# RGB_i2c_v4plusRTC.net
KiCad netlist of a schematic drawn in EAGLE
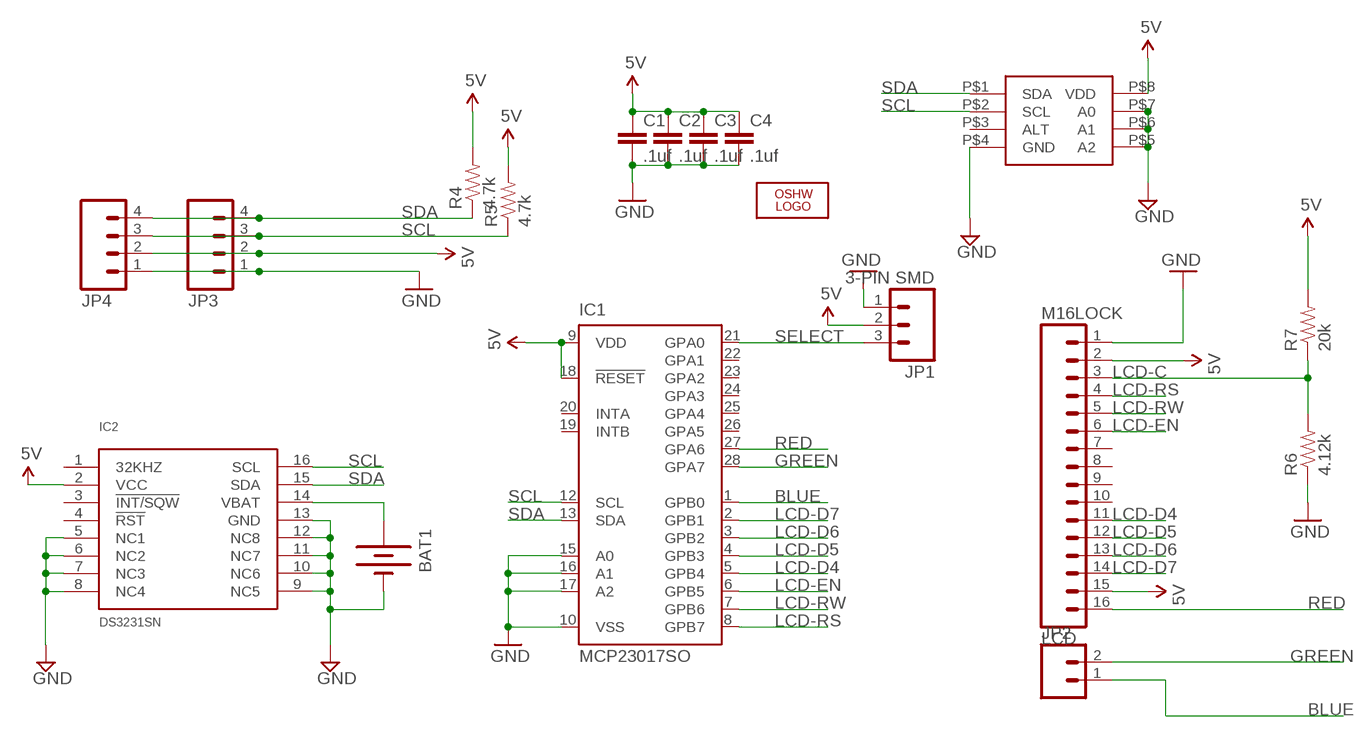
[diagram p0: schematic, sheet 1]

(export (version "E")
  (design (tool "Eeschema 10.0.6"))
  (components
    (comp (ref "BAT1")
      (value "BATTERY12MM")
      (footprint "eagle-import:BATTCON_12MM")
      (libsource (lib "eagle-import") (part "BATTERY12MM"))
    )
    (comp (ref "C1")
      (value ".1uf")
      (footprint "eagle-import:0805")
      (libsource (lib "eagle-import") (part "CAP0805"))
    )
    (comp (ref "C2")
      (value ".1uf")
      (footprint "eagle-import:0805")
      (libsource (lib "eagle-import") (part "CAP0805"))
    )
    (comp (ref "C3")
      (value ".1uf")
      (footprint "eagle-import:0805")
      (libsource (lib "eagle-import") (part "CAP0805"))
    )
    (comp (ref "C4")
      (value ".1uf")
      (footprint "eagle-import:0805")
      (libsource (lib "eagle-import") (part "CAP0805"))
    )
    (comp (ref "IC1")
      (value "MCP23017SO")
      (footprint "eagle-import:SO28W")
      (libsource (lib "eagle-import") (part "MCP23017SO"))
    )
    (comp (ref "IC2")
      (value "DS3231SN")
      (footprint "eagle-import:SO16W")
      (libsource (lib "eagle-import") (part "DS3231SN"))
    )
    (comp (ref "IC3")
      (value "MCP9808")
      (footprint "eagle-import:MSOP8")
      (libsource (lib "eagle-import") (part "MCP9808"))
    )
    (comp (ref "JP1")
      (value "3-PIN SMD")
      (footprint "eagle-import:JST-3-SMD")
      (libsource (lib "eagle-import") (part "M03JST-SMD"))
    )
    (comp (ref "JP2")
      (value "M02PTH")
      (footprint "eagle-import:1X02")
      (libsource (lib "eagle-import") (part "M02PTH"))
    )
    (comp (ref "JP3")
      (value "M04JST-PTH-VERT")
      (footprint "eagle-import:JST-4-PTH-VERT")
      (libsource (lib "eagle-import") (part "M04JST-PTH-VERT"))
    )
    (comp (ref "JP4")
      (value "M04JST-PTH-VERT")
      (footprint "eagle-import:JST-4-PTH-VERT")
      (libsource (lib "eagle-import") (part "M04JST-PTH-VERT"))
    )
    (comp (ref "LCD")
      (value "M16LOCK")
      (footprint "eagle-import:1X16_LOCK")
      (libsource (lib "eagle-import") (part "M16LOCK"))
    )
    (comp (ref "LOGO2")
      (value "OSHW_LOGO_10MILX0350-NT")
      (footprint "eagle-import:OSHW_10X350_NOTEXT")
      (libsource (lib "eagle-import") (part "OSHW_LOGO_10MILX0350-NT"))
    )
    (comp (ref "R4")
      (value "4.7k")
      (footprint "eagle-import:0805")
      (libsource (lib "eagle-import") (part "RESISTOR0805-RES"))
    )
    (comp (ref "R5")
      (value "4.7k")
      (footprint "eagle-import:0805")
      (libsource (lib "eagle-import") (part "RESISTOR0805-RES"))
    )
    (comp (ref "R6")
      (value "4.12k")
      (footprint "eagle-import:0805")
      (libsource (lib "eagle-import") (part "RESISTOR0805-RES"))
    )
    (comp (ref "R7")
      (value "20k")
      (footprint "eagle-import:0805")
      (libsource (lib "eagle-import") (part "RESISTOR0805-RES"))
    )
  )
  (nets
    (net (code "1") (name "/BLUE") (class "Default")
      (node (ref "IC1") (pin "1") (pinfunction "GPB0_1") (pintype "bidirectional"))
      (node (ref "JP2") (pin "1") (pinfunction "1_1") (pintype "passive"))
    )
    (net (code "2") (name "/GREEN") (class "Default")
      (node (ref "IC1") (pin "28") (pinfunction "GPA7_28") (pintype "bidirectional"))
      (node (ref "JP2") (pin "2") (pinfunction "2_2") (pintype "passive"))
    )
    (net (code "3") (name "/LCD-C") (class "Default")
      (node (ref "LCD") (pin "3") (pinfunction "3_3") (pintype "passive"))
      (node (ref "R6") (pin "2") (pinfunction "2_2") (pintype "passive"))
      (node (ref "R7") (pin "1") (pinfunction "1_1") (pintype "passive"))
    )
    (net (code "4") (name "/LCD-D4") (class "Default")
      (node (ref "IC1") (pin "5") (pinfunction "GPB4_5") (pintype "bidirectional"))
      (node (ref "LCD") (pin "11") (pinfunction "11_11") (pintype "passive"))
    )
    (net (code "5") (name "/LCD-D5") (class "Default")
      (node (ref "IC1") (pin "4") (pinfunction "GPB3_4") (pintype "bidirectional"))
      (node (ref "LCD") (pin "12") (pinfunction "12_12") (pintype "passive"))
    )
    (net (code "6") (name "/LCD-D6") (class "Default")
      (node (ref "IC1") (pin "3") (pinfunction "GPB2_3") (pintype "bidirectional"))
      (node (ref "LCD") (pin "13") (pinfunction "13_13") (pintype "passive"))
    )
    (net (code "7") (name "/LCD-D7") (class "Default")
      (node (ref "IC1") (pin "2") (pinfunction "GPB1_2") (pintype "bidirectional"))
      (node (ref "LCD") (pin "14") (pinfunction "14_14") (pintype "passive"))
    )
    (net (code "8") (name "/LCD-EN") (class "Default")
      (node (ref "IC1") (pin "6") (pinfunction "GPB5_6") (pintype "bidirectional"))
      (node (ref "LCD") (pin "6") (pinfunction "6_6") (pintype "passive"))
    )
    (net (code "9") (name "/LCD-RS") (class "Default")
      (node (ref "IC1") (pin "8") (pinfunction "GPB7_8") (pintype "bidirectional"))
      (node (ref "LCD") (pin "4") (pinfunction "4_4") (pintype "passive"))
    )
    (net (code "10") (name "/LCD-RW") (class "Default")
      (node (ref "IC1") (pin "7") (pinfunction "GPB6_7") (pintype "bidirectional"))
      (node (ref "LCD") (pin "5") (pinfunction "5_5") (pintype "passive"))
    )
    (net (code "11") (name "/RED") (class "Default")
      (node (ref "IC1") (pin "27") (pinfunction "GPA6_27") (pintype "bidirectional"))
      (node (ref "LCD") (pin "16") (pinfunction "16_16") (pintype "passive"))
    )
    (net (code "12") (name "/SCL") (class "Default")
      (node (ref "IC1") (pin "12") (pinfunction "SCL_12") (pintype "input"))
      (node (ref "IC2") (pin "16") (pinfunction "SCL_16") (pintype "bidirectional"))
      (node (ref "IC3") (pin "P$2") (pinfunction "SCL_P$2") (pintype "bidirectional"))
      (node (ref "JP3") (pin "3") (pinfunction "2_3") (pintype "passive"))
      (node (ref "JP4") (pin "3") (pinfunction "2_3") (pintype "passive"))
      (node (ref "R5") (pin "1") (pinfunction "1_1") (pintype "passive"))
    )
    (net (code "13") (name "/SDA") (class "Default")
      (node (ref "IC1") (pin "13") (pinfunction "SDA_13") (pintype "bidirectional"))
      (node (ref "IC2") (pin "15") (pinfunction "SDA_15") (pintype "bidirectional"))
      (node (ref "IC3") (pin "P$1") (pinfunction "SDA_P$1") (pintype "bidirectional"))
      (node (ref "JP3") (pin "4") (pinfunction "1_4") (pintype "passive"))
      (node (ref "JP4") (pin "4") (pinfunction "1_4") (pintype "passive"))
      (node (ref "R4") (pin "1") (pinfunction "1_1") (pintype "passive"))
    )
    (net (code "14") (name "/SELECT") (class "Default")
      (node (ref "IC1") (pin "21") (pinfunction "GPA0_21") (pintype "bidirectional"))
      (node (ref "JP1") (pin "3") (pinfunction "3_3") (pintype "passive"))
    )
    (net (code "15") (name "5V") (class "Default")
      (node (ref "C1") (pin "1") (pinfunction "1_1") (pintype "passive"))
      (node (ref "C2") (pin "1") (pinfunction "1_1") (pintype "passive"))
      (node (ref "C3") (pin "1") (pinfunction "1_1") (pintype "passive"))
      (node (ref "C4") (pin "1") (pinfunction "1_1") (pintype "passive"))
      (node (ref "IC1") (pin "18") (pinfunction "~{RESET}_18") (pintype "input"))
      (node (ref "IC1") (pin "9") (pinfunction "VDD_9") (pintype "power_in"))
      (node (ref "IC2") (pin "2") (pinfunction "VCC_2") (pintype "bidirectional"))
      (node (ref "IC3") (pin "P$8") (pinfunction "VDD_P$8") (pintype "bidirectional"))
      (node (ref "JP1") (pin "2") (pinfunction "2_2") (pintype "passive"))
      (node (ref "JP3") (pin "2") (pinfunction "3_2") (pintype "passive"))
      (node (ref "JP4") (pin "2") (pinfunction "3_2") (pintype "passive"))
      (node (ref "LCD") (pin "15") (pinfunction "15_15") (pintype "passive"))
      (node (ref "LCD") (pin "2") (pinfunction "2_2") (pintype "passive"))
      (node (ref "R4") (pin "2") (pinfunction "2_2") (pintype "passive"))
      (node (ref "R5") (pin "2") (pinfunction "2_2") (pintype "passive"))
      (node (ref "R7") (pin "2") (pinfunction "2_2") (pintype "passive"))
    )
    (net (code "16") (name "GND") (class "Default")
      (node (ref "BAT1") (pin "GND") (pinfunction "-_GND") (pintype "power_in"))
      (node (ref "C1") (pin "2") (pinfunction "2_2") (pintype "passive"))
      (node (ref "C2") (pin "2") (pinfunction "2_2") (pintype "passive"))
      (node (ref "C3") (pin "2") (pinfunction "2_2") (pintype "passive"))
      (node (ref "C4") (pin "2") (pinfunction "2_2") (pintype "passive"))
      (node (ref "IC1") (pin "10") (pinfunction "VSS_10") (pintype "power_in"))
      (node (ref "IC1") (pin "15") (pinfunction "A0_15") (pintype "input"))
      (node (ref "IC1") (pin "16") (pinfunction "A1_16") (pintype "input"))
      (node (ref "IC1") (pin "17") (pinfunction "A2_17") (pintype "input"))
      (node (ref "IC2") (pin "10") (pinfunction "NC6_10") (pintype "bidirectional"))
      (node (ref "IC2") (pin "11") (pinfunction "NC7_11") (pintype "bidirectional"))
      (node (ref "IC2") (pin "12") (pinfunction "NC8_12") (pintype "bidirectional"))
      (node (ref "IC2") (pin "13") (pinfunction "GND_13") (pintype "bidirectional"))
      (node (ref "IC2") (pin "5") (pinfunction "NC1_5") (pintype "bidirectional"))
      (node (ref "IC2") (pin "6") (pinfunction "NC2_6") (pintype "bidirectional"))
      (node (ref "IC2") (pin "7") (pinfunction "NC3_7") (pintype "bidirectional"))
      (node (ref "IC2") (pin "8") (pinfunction "NC4_8") (pintype "bidirectional"))
      (node (ref "IC2") (pin "9") (pinfunction "NC5_9") (pintype "bidirectional"))
      (node (ref "IC3") (pin "P$4") (pinfunction "GND_P$4") (pintype "bidirectional"))
      (node (ref "IC3") (pin "P$5") (pinfunction "A2_P$5") (pintype "bidirectional"))
      (node (ref "IC3") (pin "P$6") (pinfunction "A1_P$6") (pintype "bidirectional"))
      (node (ref "IC3") (pin "P$7") (pinfunction "A0_P$7") (pintype "bidirectional"))
      (node (ref "JP1") (pin "1") (pinfunction "1_1") (pintype "passive"))
      (node (ref "JP3") (pin "1") (pinfunction "4_1") (pintype "passive"))
      (node (ref "JP4") (pin "1") (pinfunction "4_1") (pintype "passive"))
      (node (ref "LCD") (pin "1") (pinfunction "1_1") (pintype "passive"))
      (node (ref "R6") (pin "1") (pinfunction "1_1") (pintype "passive"))
    )
    (net (code "17") (name "Net-(BAT1-+)") (class "Default")
      (node (ref "BAT1") (pin "PWR@1") (pinfunction "+_PWR@1") (pintype "power_in"))
      (node (ref "IC2") (pin "14") (pinfunction "VBAT_14") (pintype "bidirectional"))
    )
    (net (code "18") (name "unconnected-(IC1-GPA1-Pad22)") (class "Default")
      (node (ref "IC1") (pin "22") (pinfunction "GPA1_22") (pintype "bidirectional"))
    )
    (net (code "19") (name "unconnected-(IC1-GPA2-Pad23)") (class "Default")
      (node (ref "IC1") (pin "23") (pinfunction "GPA2_23") (pintype "bidirectional"))
    )
    (net (code "20") (name "unconnected-(IC1-GPA3-Pad24)") (class "Default")
      (node (ref "IC1") (pin "24") (pinfunction "GPA3_24") (pintype "bidirectional"))
    )
    (net (code "21") (name "unconnected-(IC1-GPA4-Pad25)") (class "Default")
      (node (ref "IC1") (pin "25") (pinfunction "GPA4_25") (pintype "bidirectional"))
    )
    (net (code "22") (name "unconnected-(IC1-GPA5-Pad26)") (class "Default")
      (node (ref "IC1") (pin "26") (pinfunction "GPA5_26") (pintype "bidirectional"))
    )
    (net (code "23") (name "unconnected-(IC1-INTA-Pad20)") (class "Default")
      (node (ref "IC1") (pin "20") (pinfunction "INTA_20") (pintype "output"))
    )
    (net (code "24") (name "unconnected-(IC1-INTB-Pad19)") (class "Default")
      (node (ref "IC1") (pin "19") (pinfunction "INTB_19") (pintype "output"))
    )
    (net (code "25") (name "unconnected-(IC2-32KHZ-Pad1)") (class "Default")
      (node (ref "IC2") (pin "1") (pinfunction "32KHZ_1") (pintype "bidirectional"))
    )
    (net (code "26") (name "unconnected-(IC2-~{INT{slash}SQW}-Pad3)") (class "Default")
      (node (ref "IC2") (pin "3") (pinfunction "~{INT/SQW}_3") (pintype "bidirectional"))
    )
    (net (code "27") (name "unconnected-(IC2-~{RST}-Pad4)") (class "Default")
      (node (ref "IC2") (pin "4") (pinfunction "~{RST}_4") (pintype "bidirectional"))
    )
    (net (code "28") (name "unconnected-(IC3-ALT-PadP$3)") (class "Default")
      (node (ref "IC3") (pin "P$3") (pinfunction "ALT_P$3") (pintype "bidirectional"))
    )
    (net (code "29") (name "unconnected-(LCD-Pad7)") (class "Default")
      (node (ref "LCD") (pin "7") (pinfunction "7_7") (pintype "passive"))
    )
    (net (code "30") (name "unconnected-(LCD-Pad8)") (class "Default")
      (node (ref "LCD") (pin "8") (pinfunction "8_8") (pintype "passive"))
    )
    (net (code "31") (name "unconnected-(LCD-Pad9)") (class "Default")
      (node (ref "LCD") (pin "9") (pinfunction "9_9") (pintype "passive"))
    )
    (net (code "32") (name "unconnected-(LCD-Pad10)") (class "Default")
      (node (ref "LCD") (pin "10") (pinfunction "10_10") (pintype "passive"))
    )
  )
)
